# logi-mark1-edu.net
KiCad netlist of a schematic drawn in Altium Designer
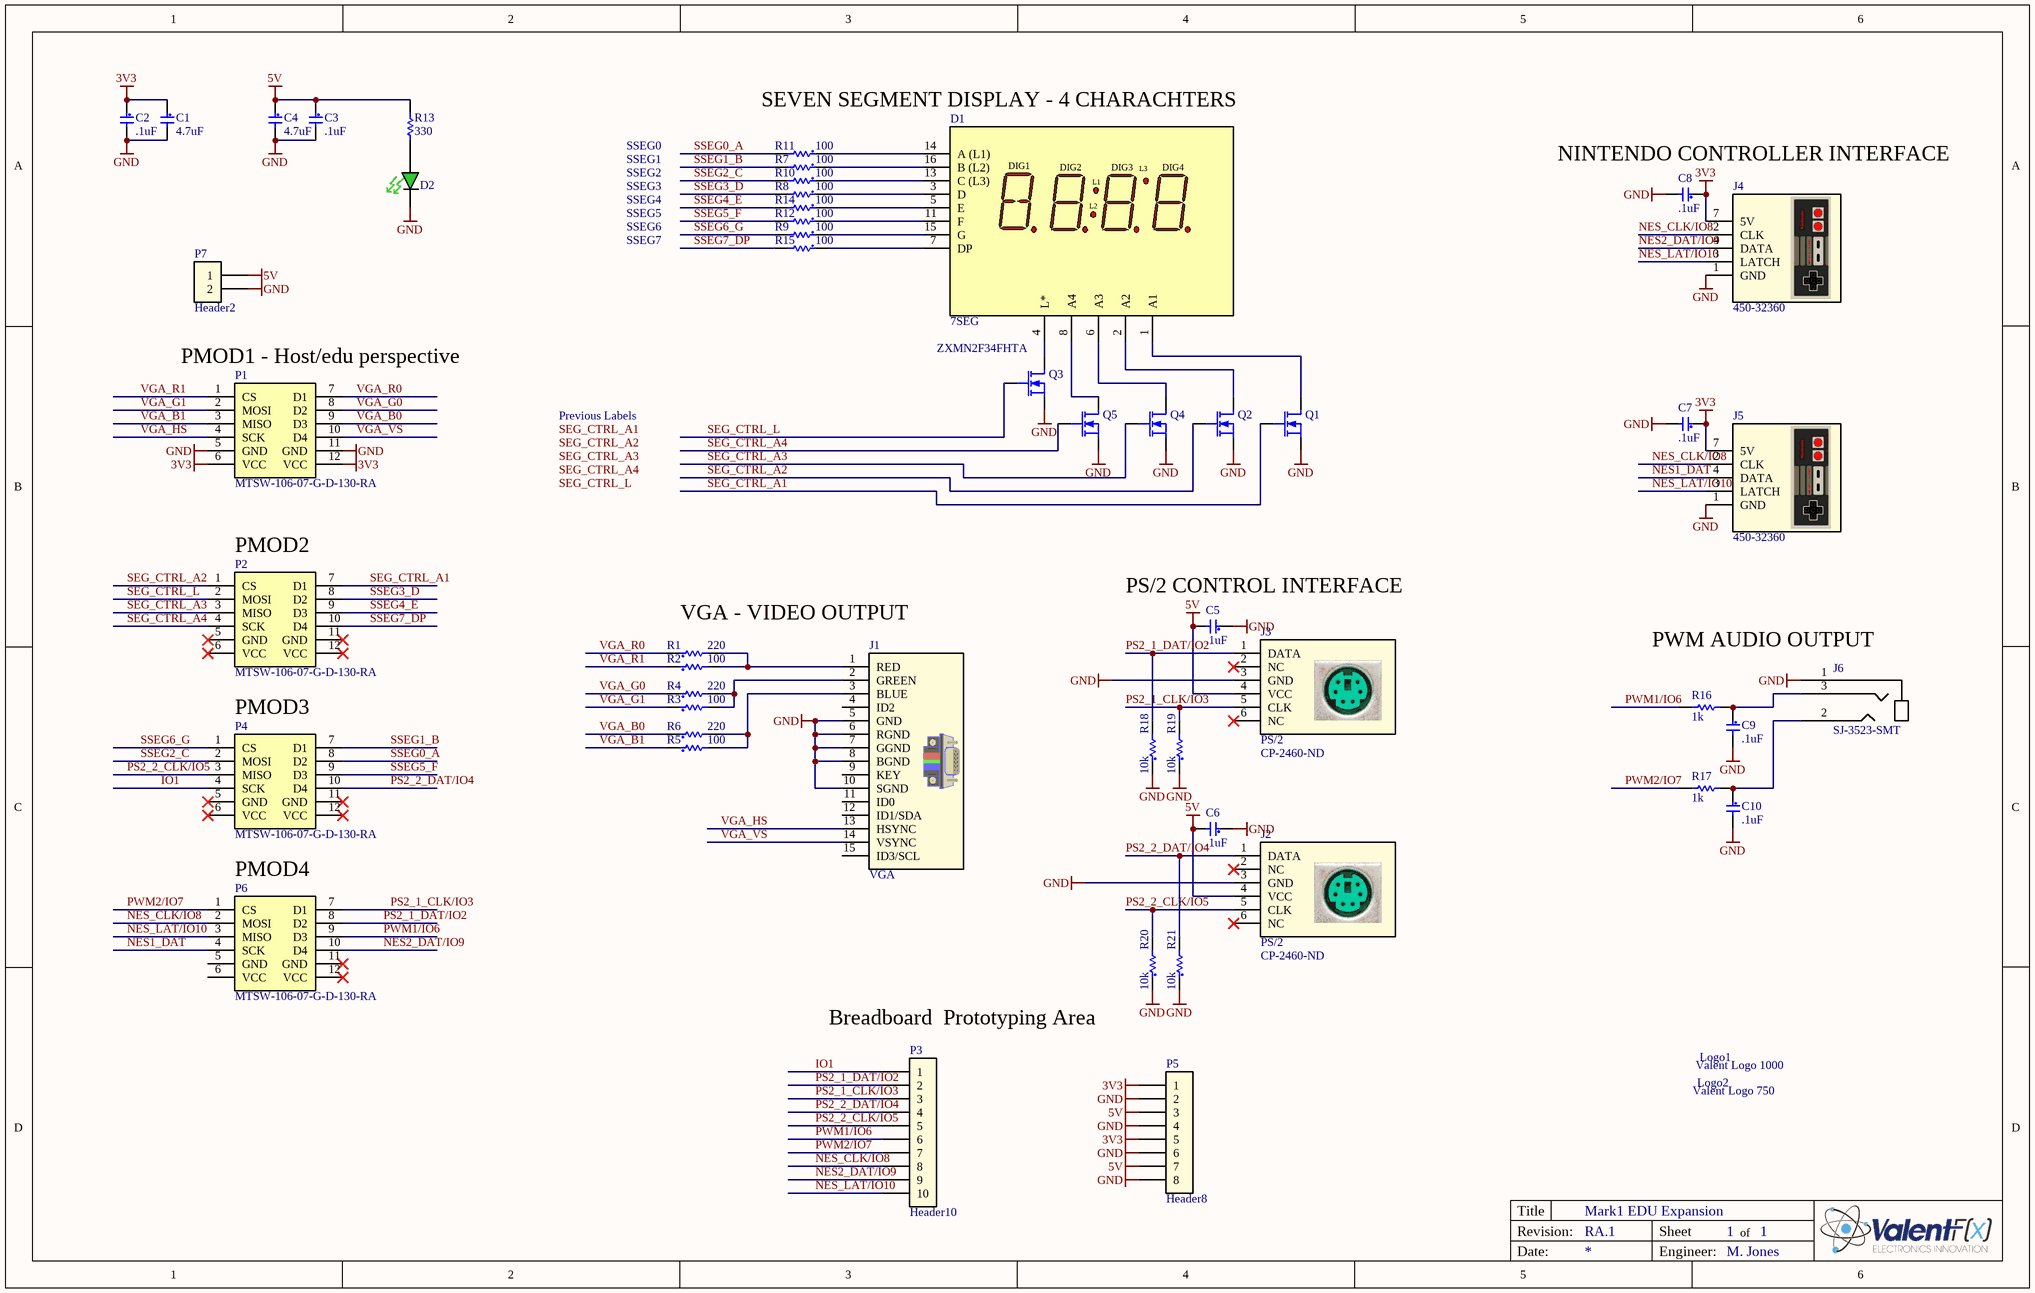
[diagram p0: logi-mark1-edu.SchDoc]

(export (version "E")
  (design (tool "Eeschema 10.0.6"))
  (components
    (comp (ref "C1")
      (value "4.7uF")
      (footprint "mRCL:C0603")
      (description "4.7uF 10volts Y5V +80-20% (MLCC) - SMD/SMT 0603")
      (fields
        (field (name "MANUFACTURER") "Murata")
        (field (name "MANUFACTURER PART NUMBER") "GRM188F51A475ZE20D")
      )
      (libsource (lib "mCapacitors") (part "C0603 - GRM188F51A475ZE20D"))
    )
    (comp (ref "C2")
      (value ".1uF")
      (footprint "mRCL:C0603")
      (description "0.1uF 50volts X7R 10% MLCC SMD/SMT 0603")
      (fields
        (field (name "MANUFACTURER") "Murata")
        (field (name "MANUFACTURER PART NUMBER") "GRM188R71H104KA93D")
      )
      (libsource (lib "mCapacitors") (part "C0603 - GRM188R71H104KA93D"))
    )
    (comp (ref "C3")
      (value ".1uF")
      (footprint "mRCL:C0603")
      (description "0.1uF 50volts X7R 10% MLCC SMD/SMT 0603")
      (fields
        (field (name "MANUFACTURER") "Murata")
        (field (name "MANUFACTURER PART NUMBER") "GRM188R71H104KA93D")
      )
      (libsource (lib "mCapacitors") (part "C0603 - GRM188R71H104KA93D"))
    )
    (comp (ref "C4")
      (value "4.7uF")
      (footprint "mRCL:C0603")
      (description "4.7uF 10volts Y5V +80-20% (MLCC) - SMD/SMT 0603")
      (fields
        (field (name "MANUFACTURER") "Murata")
        (field (name "MANUFACTURER PART NUMBER") "GRM188F51A475ZE20D")
      )
      (libsource (lib "mCapacitors") (part "C0603 - GRM188F51A475ZE20D"))
    )
    (comp (ref "C5")
      (value ".1uF")
      (footprint "mRCL:C0603")
      (description "0.1uF 50volts X7R 10% MLCC SMD/SMT 0603")
      (fields
        (field (name "MANUFACTURER") "Murata")
        (field (name "MANUFACTURER PART NUMBER") "GRM188R71H104KA93D")
      )
      (libsource (lib "mCapacitors") (part "C0603 - GRM188R71H104KA93D"))
    )
    (comp (ref "C6")
      (value ".1uF")
      (footprint "mRCL:C0603")
      (description "0.1uF 50volts X7R 10% MLCC SMD/SMT 0603")
      (fields
        (field (name "MANUFACTURER") "Murata")
        (field (name "MANUFACTURER PART NUMBER") "GRM188R71H104KA93D")
      )
      (libsource (lib "mCapacitors") (part "C0603 - GRM188R71H104KA93D"))
    )
    (comp (ref "C7")
      (value ".1uF")
      (footprint "mRCL:C0603")
      (description "0.1uF 50volts X7R 10% MLCC SMD/SMT 0603")
      (fields
        (field (name "MANUFACTURER") "Murata")
        (field (name "MANUFACTURER PART NUMBER") "GRM188R71H104KA93D")
      )
      (libsource (lib "mCapacitors") (part "C0603 - GRM188R71H104KA93D"))
    )
    (comp (ref "C8")
      (value ".1uF")
      (footprint "mRCL:C0603")
      (description "0.1uF 50volts X7R 10% MLCC SMD/SMT 0603")
      (fields
        (field (name "MANUFACTURER") "Murata")
        (field (name "MANUFACTURER PART NUMBER") "GRM188R71H104KA93D")
      )
      (libsource (lib "mCapacitors") (part "C0603 - GRM188R71H104KA93D"))
    )
    (comp (ref "C9")
      (value ".1uF")
      (footprint "mRCL:C0603")
      (description "0.1uF 50volts X7R 10% MLCC SMD/SMT 0603")
      (fields
        (field (name "MANUFACTURER") "Murata")
        (field (name "MANUFACTURER PART NUMBER") "GRM188R71H104KA93D")
      )
      (libsource (lib "mCapacitors") (part "C0603 - GRM188R71H104KA93D"))
    )
    (comp (ref "C10")
      (value ".1uF")
      (footprint "mRCL:C0603")
      (description "0.1uF 50volts X7R 10% MLCC SMD/SMT 0603")
      (fields
        (field (name "MANUFACTURER") "Murata")
        (field (name "MANUFACTURER PART NUMBER") "GRM188R71H104KA93D")
      )
      (libsource (lib "mCapacitors") (part "C0603 - GRM188R71H104KA93D"))
    )
    (comp (ref "D1")
      (value "7SEG")
      (footprint "LED - SSEG - LTC-4727JR")
      (description "LED Displays & Accessories 4 Digit, Red Low Current")
      (fields (field (name "MANUFACTURER") "Lite-On") (field (name "MANUFACTURER PART NUMBER") "LTC-4727JR"))
      (libsource (lib "eDiode") (part "LED - SSEG - LTC-4727JR"))
    )
    (comp (ref "D2")
      (value "LED 1.6X0.8MM 570NM GRN CLR SMD")
      (footprint "LED_0603 - GREEN")
      (fields
        (field (name "MANUFACTURER") "Kingbright Corp")
        (field (name "MANUFACTURER PART NUMBER") "APT1608CGCK")
      )
      (libsource (lib "eDiode") (part "APT1608CGCK"))
    )
    (comp (ref "J1")
      (value "VGA")
      (footprint "econnector:1-1734530-1")
      (description "CONN HD D-SUB RCPT R/A 15POS")
      (fields
        (field (name "MANUFACTURER") "TE Connectivity")
        (field (name "MANUFACTURER PART NUMBER") "1-1734530-1")
      )
      (libsource (lib "eConnector") (part "VGA - 1-1734530-1"))
    )
    (comp (ref "J2")
      (value "PS/2")
      (footprint "mconnector:MD-60S - PS/2")
      (description "CONN MINIDIN RECPT UNSHIELD 6POS - PS/2 mouse - keybaord")
      (fields
        (field (name "MANUFACTURER") "CUI Inc")
        (field (name "MANUFACTURER PART NUMBER") "MD-60S")
        (field (name "SUPPLIER PART NUMBER 1") "CP-2460-ND")
      )
      (libsource (lib "mConnector") (part "Con - D-60S"))
    )
    (comp (ref "J3")
      (value "PS/2")
      (footprint "mconnector:MD-60S - PS/2")
      (description "CONN MINIDIN RECPT UNSHIELD 6POS - PS/2 mouse - keybaord")
      (fields
        (field (name "MANUFACTURER") "CUI Inc")
        (field (name "MANUFACTURER PART NUMBER") "MD-60S")
        (field (name "SUPPLIER PART NUMBER 1") "CP-2460-ND")
      )
      (libsource (lib "mConnector") (part "Con - D-60S"))
    )
    (comp (ref "J4")
      (value "450-32360")
      (footprint "NES - 450-32360")
      (description "NES CONTROLLER SOCKET")
      (fields (field (name "MANUFACTURER") "Parallax Inc"))
      (libsource (lib "mConnector") (part "450-32360"))
    )
    (comp (ref "J5")
      (value "450-32360")
      (footprint "NES - 450-32360")
      (description "NES CONTROLLER SOCKET")
      (fields (field (name "MANUFACTURER") "Parallax Inc"))
      (libsource (lib "mConnector") (part "450-32360"))
    )
    (comp (ref "J6")
      (value "SJ-3523-SMT")
      (footprint "SJ-3523-SMT")
      (description "CONN AUDIO JACK 3.5MM STEREO SMD")
      (fields (field (name "MANUFACTURER") "CUI Inc") (field (name "SOURCE") "Digikey"))
      (libsource (lib "eConnector") (part "SJ-3523-SMT"))
    )
    (comp (ref "Logo1")
      (value "Valent Logo 1000")
      (footprint "ValentFX_1000")
      (libsource (lib "mLogos") (part "Valent Logo 1000"))
    )
    (comp (ref "Logo2")
      (value "Valent Logo 750")
      (footprint "ValentFX_750")
      (libsource (lib "mLogos") (part "Valent Logo 750"))
    )
    (comp (ref "P1")
      (value "MTSW-106-07-G-D-130-RA")
      (footprint "mconnector:PMOD HEADER - Male")
      (description "Samtec Male Conn Unshrouded Header HDR 12 POS 2.54mm Solder RA Thru-Hole")
      (fields (field (name "MANUFACTURER") "Samtec"))
      (libsource (lib "mConnector") (part "P-MOD - MTSW-106-07-G-D-130-RA"))
    )
    (comp (ref "P2")
      (value "MTSW-106-07-G-D-130-RA")
      (footprint "mconnector:PMOD HEADER - Male")
      (description "Samtec Male Conn Unshrouded Header HDR 12 POS 2.54mm Solder RA Thru-Hole")
      (fields (field (name "MANUFACTURER") "Samtec"))
      (libsource (lib "mConnector") (part "P-MOD - MTSW-106-07-G-D-130-RA"))
    )
    (comp (ref "P3")
      (value "Header10")
      (footprint "HEADER_10_40_100THRU SIP")
      (description "Header 10 pin")
      (libsource (lib "mConnector") (part "Header10"))
    )
    (comp (ref "P4")
      (value "MTSW-106-07-G-D-130-RA")
      (footprint "mconnector:PMOD HEADER - Male")
      (description "Samtec Male Conn Unshrouded Header HDR 12 POS 2.54mm Solder RA Thru-Hole")
      (fields (field (name "MANUFACTURER") "Samtec"))
      (libsource (lib "mConnector") (part "P-MOD - MTSW-106-07-G-D-130-RA"))
    )
    (comp (ref "P5")
      (value "Header8")
      (footprint "HEADER_8_40_100THRU SIP")
      (description "Header 8 pin")
      (libsource (lib "mConnector") (part "Header8"))
    )
    (comp (ref "P6")
      (value "MTSW-106-07-G-D-130-RA")
      (footprint "mconnector:PMOD HEADER - Male")
      (description "Samtec Male Conn Unshrouded Header HDR 12 POS 2.54mm Solder RA Thru-Hole")
      (fields (field (name "MANUFACTURER") "Samtec"))
      (libsource (lib "mConnector") (part "P-MOD - MTSW-106-07-G-D-130-RA"))
    )
    (comp (ref "P7")
      (value "Header2")
      (footprint "HEADER_2_40_100 THRU SIP")
      (description "Header 2 pin")
      (libsource (lib "mConnector") (part "Header2"))
    )
    (comp (ref "Q1")
      (value "ZXMN2F34FHTA")
      (footprint "SOT-23")
      (description "MOSFET N-CHAN 20V SOT23-3")
      (fields (field (name "MANUFACTURER") "Diodes/Zetex"))
      (libsource (lib "eTransistor") (part "ZXMN2F34FHTA"))
    )
    (comp (ref "Q2")
      (value "ZXMN2F34FHTA")
      (footprint "SOT-23")
      (description "MOSFET N-CHAN 20V SOT23-3")
      (fields (field (name "MANUFACTURER") "Diodes/Zetex"))
      (libsource (lib "eTransistor") (part "ZXMN2F34FHTA"))
    )
    (comp (ref "Q3")
      (value "ZXMN2F34FHTA")
      (footprint "SOT-23")
      (description "MOSFET N-CHAN 20V SOT23-3")
      (fields (field (name "MANUFACTURER") "Diodes/Zetex"))
      (libsource (lib "eTransistor") (part "ZXMN2F34FHTA"))
    )
    (comp (ref "Q4")
      (value "ZXMN2F34FHTA")
      (footprint "SOT-23")
      (description "MOSFET N-CHAN 20V SOT23-3")
      (fields (field (name "MANUFACTURER") "Diodes/Zetex"))
      (libsource (lib "eTransistor") (part "ZXMN2F34FHTA"))
    )
    (comp (ref "Q5")
      (value "ZXMN2F34FHTA")
      (footprint "SOT-23")
      (description "MOSFET N-CHAN 20V SOT23-3")
      (fields (field (name "MANUFACTURER") "Diodes/Zetex"))
      (libsource (lib "eTransistor") (part "ZXMN2F34FHTA"))
    )
    (comp (ref "R1")
      (value "220")
      (footprint "mRCL:R0603")
      (description "220 - thick Film Resistors - SMD 0603 220ohms 1% Tol")
      (fields
        (field (name "MANUFACTURER") "Panasonic - ECG")
        (field (name "MANUFACTURER PART NUMBER") "ERJ-3EKF2200V")
      )
      (libsource (lib "mResistors") (part "R0603 - ERJ-3EKF2200V"))
    )
    (comp (ref "R2")
      (value "100")
      (footprint "mRCL:R0603")
      (description "100 ohms 1% Thick Film Resistors - SMD 1/10watt")
      (fields
        (field (name "MANUFACTURER") "Vishay/Dale")
        (field (name "MANUFACTURER PART NUMBER") "CRCW0603100RFKEA")
      )
      (libsource (lib "mResistors") (part "R0603 - CRCW0603100RFKEA"))
    )
    (comp (ref "R3")
      (value "100")
      (footprint "mRCL:R0603")
      (description "100 ohms 1% Thick Film Resistors - SMD 1/10watt")
      (fields
        (field (name "MANUFACTURER") "Vishay/Dale")
        (field (name "MANUFACTURER PART NUMBER") "CRCW0603100RFKEA")
      )
      (libsource (lib "mResistors") (part "R0603 - CRCW0603100RFKEA"))
    )
    (comp (ref "R4")
      (value "220")
      (footprint "mRCL:R0603")
      (description "220 - thick Film Resistors - SMD 0603 220ohms 1% Tol")
      (fields
        (field (name "MANUFACTURER") "Panasonic - ECG")
        (field (name "MANUFACTURER PART NUMBER") "ERJ-3EKF2200V")
      )
      (libsource (lib "mResistors") (part "R0603 - ERJ-3EKF2200V"))
    )
    (comp (ref "R5")
      (value "100")
      (footprint "mRCL:R0603")
      (description "100 ohms 1% Thick Film Resistors - SMD 1/10watt")
      (fields
        (field (name "MANUFACTURER") "Vishay/Dale")
        (field (name "MANUFACTURER PART NUMBER") "CRCW0603100RFKEA")
      )
      (libsource (lib "mResistors") (part "R0603 - CRCW0603100RFKEA"))
    )
    (comp (ref "R6")
      (value "220")
      (footprint "mRCL:R0603")
      (description "220 - thick Film Resistors - SMD 0603 220ohms 1% Tol")
      (fields
        (field (name "MANUFACTURER") "Panasonic - ECG")
        (field (name "MANUFACTURER PART NUMBER") "ERJ-3EKF2200V")
      )
      (libsource (lib "mResistors") (part "R0603 - ERJ-3EKF2200V"))
    )
    (comp (ref "R7")
      (value "100")
      (footprint "R0603")
      (description "RES 10.0K OHM 1/10W 1% 0603 SMD")
      (fields
        (field (name "MANUFACTURER") "Panasonic - ECG")
        (field (name "MANUFACTURER PART NUMBER") "ERJ-3EKF1002V")
      )
      (libsource (lib "myGeneral") (part "Res-Eli"))
    )
    (comp (ref "R8")
      (value "100")
      (footprint "R0603")
      (description "RES 10.0K OHM 1/10W 1% 0603 SMD")
      (fields
        (field (name "MANUFACTURER") "Panasonic - ECG")
        (field (name "MANUFACTURER PART NUMBER") "ERJ-3EKF1002V")
      )
      (libsource (lib "myGeneral") (part "Res-Eli"))
    )
    (comp (ref "R9")
      (value "100")
      (footprint "R0603")
      (description "RES 10.0K OHM 1/10W 1% 0603 SMD")
      (fields
        (field (name "MANUFACTURER") "Panasonic - ECG")
        (field (name "MANUFACTURER PART NUMBER") "ERJ-3EKF1002V")
      )
      (libsource (lib "myGeneral") (part "Res-Eli"))
    )
    (comp (ref "R10")
      (value "100")
      (footprint "R0603")
      (description "RES 10.0K OHM 1/10W 1% 0603 SMD")
      (fields
        (field (name "MANUFACTURER") "Panasonic - ECG")
        (field (name "MANUFACTURER PART NUMBER") "ERJ-3EKF1002V")
      )
      (libsource (lib "myGeneral") (part "Res-Eli"))
    )
    (comp (ref "R11")
      (value "100")
      (footprint "R0603")
      (description "RES 10.0K OHM 1/10W 1% 0603 SMD")
      (fields
        (field (name "MANUFACTURER") "Panasonic - ECG")
        (field (name "MANUFACTURER PART NUMBER") "ERJ-3EKF1002V")
      )
      (libsource (lib "myGeneral") (part "Res-Eli"))
    )
    (comp (ref "R12")
      (value "100")
      (footprint "R0603")
      (description "RES 10.0K OHM 1/10W 1% 0603 SMD")
      (fields
        (field (name "MANUFACTURER") "Panasonic - ECG")
        (field (name "MANUFACTURER PART NUMBER") "ERJ-3EKF1002V")
      )
      (libsource (lib "myGeneral") (part "Res-Eli"))
    )
    (comp (ref "R13")
      (value "330")
      (footprint "R0603")
      (description "RES 330 OHM 1/10W 1% 0603 SMD")
      (fields
        (field (name "MANUFACTURER") "Panasonic - ECG")
        (field (name "MANUFACTURER PART NUMBER") "ERJ-3EKF3300V")
      )
      (libsource (lib "eResistors") (part "ERJ-3EKF3300V"))
    )
    (comp (ref "R14")
      (value "100")
      (footprint "R0603")
      (description "RES 10.0K OHM 1/10W 1% 0603 SMD")
      (fields
        (field (name "MANUFACTURER") "Panasonic - ECG")
        (field (name "MANUFACTURER PART NUMBER") "ERJ-3EKF1002V")
      )
      (libsource (lib "myGeneral") (part "Res-Eli"))
    )
    (comp (ref "R15")
      (value "100")
      (footprint "R0603")
      (description "RES 10.0K OHM 1/10W 1% 0603 SMD")
      (fields
        (field (name "MANUFACTURER") "Panasonic - ECG")
        (field (name "MANUFACTURER PART NUMBER") "ERJ-3EKF1002V")
      )
      (libsource (lib "myGeneral") (part "Res-Eli"))
    )
    (comp (ref "R16")
      (value "1k")
      (footprint "R0603")
      (description "RES 1.00K OHM 1/10W 1% 0603 SMD")
      (fields
        (field (name "MANUFACTURER") "Panasonic - ECG")
        (field (name "MANUFACTURER PART NUMBER") "ERJ-3EKF1001V")
      )
      (libsource (lib "eResistors") (part "ERJ-3EKF1001V"))
    )
    (comp (ref "R17")
      (value "1k")
      (footprint "R0603")
      (description "RES 1.00K OHM 1/10W 1% 0603 SMD")
      (fields
        (field (name "MANUFACTURER") "Panasonic - ECG")
        (field (name "MANUFACTURER PART NUMBER") "ERJ-3EKF1001V")
      )
      (libsource (lib "eResistors") (part "ERJ-3EKF1001V"))
    )
    (comp (ref "R18")
      (value "10k")
      (footprint "mRCL:R0603")
      (description "10k Thick Film Resistors - SMD 1/10watt 10Kohms 1%")
      (fields
        (field (name "MANUFACTURER") "Vishay Dale")
        (field (name "MANUFACTURER PART NUMBER") "CRCW060310K0FKEA")
      )
      (libsource (lib "mResistors") (part "R0603 - CRCW060310K0FKEA"))
    )
    (comp (ref "R19")
      (value "10k")
      (footprint "mRCL:R0603")
      (description "10k Thick Film Resistors - SMD 1/10watt 10Kohms 1%")
      (fields
        (field (name "MANUFACTURER") "Vishay Dale")
        (field (name "MANUFACTURER PART NUMBER") "CRCW060310K0FKEA")
      )
      (libsource (lib "mResistors") (part "R0603 - CRCW060310K0FKEA"))
    )
    (comp (ref "R20")
      (value "10k")
      (footprint "mRCL:R0603")
      (description "10k Thick Film Resistors - SMD 1/10watt 10Kohms 1%")
      (fields
        (field (name "MANUFACTURER") "Vishay Dale")
        (field (name "MANUFACTURER PART NUMBER") "CRCW060310K0FKEA")
      )
      (libsource (lib "mResistors") (part "R0603 - CRCW060310K0FKEA"))
    )
    (comp (ref "R21")
      (value "10k")
      (footprint "mRCL:R0603")
      (description "10k Thick Film Resistors - SMD 1/10watt 10Kohms 1%")
      (fields
        (field (name "MANUFACTURER") "Vishay Dale")
        (field (name "MANUFACTURER PART NUMBER") "CRCW060310K0FKEA")
      )
      (libsource (lib "mResistors") (part "R0603 - CRCW060310K0FKEA"))
    )
  )
  (nets
    (net (code "1") (name "/IO1") (class "Default")
      (node (ref "P3") (pin "1") (pinfunction "1_1") (pintype "passive"))
      (node (ref "P4") (pin "4") (pinfunction "SCK_4") (pintype "power_in"))
    )
    (net (code "2") (name "/NES1_DAT") (class "Default")
      (node (ref "J5") (pin "4") (pinfunction "DATA_4") (pintype "passive"))
      (node (ref "P6") (pin "4") (pinfunction "SCK_4") (pintype "power_in"))
    )
    (net (code "3") (name "/NES2_DAT{slash}IO9") (class "Default")
      (node (ref "J4") (pin "4") (pinfunction "DATA_4") (pintype "passive"))
      (node (ref "P3") (pin "9") (pinfunction "9_9") (pintype "passive"))
      (node (ref "P6") (pin "10") (pinfunction "D4_10") (pintype "power_in"))
    )
    (net (code "4") (name "/NES_CLK{slash}IO8") (class "Default")
      (node (ref "J4") (pin "2") (pinfunction "CLK_2") (pintype "passive"))
      (node (ref "J5") (pin "2") (pinfunction "CLK_2") (pintype "passive"))
      (node (ref "P3") (pin "8") (pinfunction "8_8") (pintype "passive"))
      (node (ref "P6") (pin "2") (pinfunction "MOSI_2") (pintype "power_in"))
    )
    (net (code "5") (name "/NES_LAT{slash}IO10") (class "Default")
      (node (ref "J4") (pin "3") (pinfunction "LATCH_3") (pintype "passive"))
      (node (ref "J5") (pin "3") (pinfunction "LATCH_3") (pintype "passive"))
      (node (ref "P3") (pin "10") (pinfunction "10_10") (pintype "passive"))
      (node (ref "P6") (pin "3") (pinfunction "MISO_3") (pintype "power_in"))
    )
    (net (code "6") (name "/PS2_1_CLK{slash}IO3") (class "Default")
      (node (ref "J3") (pin "5") (pinfunction "CLK_5") (pintype "passive"))
      (node (ref "P3") (pin "3") (pinfunction "3_3") (pintype "passive"))
      (node (ref "P6") (pin "7") (pinfunction "D1_7") (pintype "power_in"))
      (node (ref "R19") (pin "2") (pinfunction "2_2") (pintype "passive"))
    )
    (net (code "7") (name "/PS2_1_DAT{slash}IO2") (class "Default")
      (node (ref "J3") (pin "1") (pinfunction "DATA_1") (pintype "passive"))
      (node (ref "P3") (pin "2") (pinfunction "2_2") (pintype "passive"))
      (node (ref "P6") (pin "8") (pinfunction "D2_8") (pintype "power_in"))
      (node (ref "R18") (pin "2") (pinfunction "2_2") (pintype "passive"))
    )
    (net (code "8") (name "/PS2_2_CLK{slash}IO5") (class "Default")
      (node (ref "J2") (pin "5") (pinfunction "CLK_5") (pintype "passive"))
      (node (ref "P3") (pin "5") (pinfunction "5_5") (pintype "passive"))
      (node (ref "P4") (pin "3") (pinfunction "MISO_3") (pintype "power_in"))
      (node (ref "R20") (pin "2") (pinfunction "2_2") (pintype "passive"))
    )
    (net (code "9") (name "/PS2_2_DAT{slash}IO4") (class "Default")
      (node (ref "J2") (pin "1") (pinfunction "DATA_1") (pintype "passive"))
      (node (ref "P3") (pin "4") (pinfunction "4_4") (pintype "passive"))
      (node (ref "P4") (pin "10") (pinfunction "D4_10") (pintype "power_in"))
      (node (ref "R21") (pin "2") (pinfunction "2_2") (pintype "passive"))
    )
    (net (code "10") (name "/PWM1{slash}IO6") (class "Default")
      (node (ref "P3") (pin "6") (pinfunction "6_6") (pintype "passive"))
      (node (ref "P6") (pin "9") (pinfunction "D3_9") (pintype "power_in"))
      (node (ref "R16") (pin "1") (pinfunction "1_1") (pintype "passive"))
    )
    (net (code "11") (name "/PWM2{slash}IO7") (class "Default")
      (node (ref "P3") (pin "7") (pinfunction "7_7") (pintype "passive"))
      (node (ref "P6") (pin "1") (pinfunction "CS_1") (pintype "power_in"))
      (node (ref "R17") (pin "1") (pinfunction "1_1") (pintype "passive"))
    )
    (net (code "12") (name "/SEG_CTRL_A1") (class "Default")
      (node (ref "P2") (pin "7") (pinfunction "D1_7") (pintype "power_in"))
      (node (ref "Q1") (pin "1") (pinfunction "G_1") (pintype "passive"))
    )
    (net (code "13") (name "/SEG_CTRL_A2") (class "Default")
      (node (ref "P2") (pin "1") (pinfunction "CS_1") (pintype "power_in"))
      (node (ref "Q2") (pin "1") (pinfunction "G_1") (pintype "passive"))
    )
    (net (code "14") (name "/SEG_CTRL_A3") (class "Default")
      (node (ref "P2") (pin "3") (pinfunction "MISO_3") (pintype "power_in"))
      (node (ref "Q4") (pin "1") (pinfunction "G_1") (pintype "passive"))
    )
    (net (code "15") (name "/SEG_CTRL_A4") (class "Default")
      (node (ref "P2") (pin "4") (pinfunction "SCK_4") (pintype "power_in"))
      (node (ref "Q5") (pin "1") (pinfunction "G_1") (pintype "passive"))
    )
    (net (code "16") (name "/SEG_CTRL_L") (class "Default")
      (node (ref "P2") (pin "2") (pinfunction "MOSI_2") (pintype "power_in"))
      (node (ref "Q3") (pin "1") (pinfunction "G_1") (pintype "passive"))
    )
    (net (code "17") (name "/SSEG0_A") (class "Default")
      (node (ref "P4") (pin "8") (pinfunction "D2_8") (pintype "power_in"))
      (node (ref "R11") (pin "2") (pinfunction "2_2") (pintype "passive"))
    )
    (net (code "18") (name "/SSEG1_B") (class "Default")
      (node (ref "P4") (pin "7") (pinfunction "D1_7") (pintype "power_in"))
      (node (ref "R7") (pin "2") (pinfunction "2_2") (pintype "passive"))
    )
    (net (code "19") (name "/SSEG2_C") (class "Default")
      (node (ref "P4") (pin "2") (pinfunction "MOSI_2") (pintype "power_in"))
      (node (ref "R10") (pin "2") (pinfunction "2_2") (pintype "passive"))
    )
    (net (code "20") (name "/SSEG3_D") (class "Default")
      (node (ref "P2") (pin "8") (pinfunction "D2_8") (pintype "power_in"))
      (node (ref "R8") (pin "2") (pinfunction "2_2") (pintype "passive"))
    )
    (net (code "21") (name "/SSEG4_E") (class "Default")
      (node (ref "P2") (pin "9") (pinfunction "D3_9") (pintype "power_in"))
      (node (ref "R14") (pin "2") (pinfunction "2_2") (pintype "passive"))
    )
    (net (code "22") (name "/SSEG5_F") (class "Default")
      (node (ref "P4") (pin "9") (pinfunction "D3_9") (pintype "power_in"))
      (node (ref "R12") (pin "2") (pinfunction "2_2") (pintype "passive"))
    )
    (net (code "23") (name "/SSEG6_G") (class "Default")
      (node (ref "P4") (pin "1") (pinfunction "CS_1") (pintype "power_in"))
      (node (ref "R9") (pin "2") (pinfunction "2_2") (pintype "passive"))
    )
    (net (code "24") (name "/SSEG7_DP") (class "Default")
      (node (ref "P2") (pin "10") (pinfunction "D4_10") (pintype "power_in"))
      (node (ref "R15") (pin "2") (pinfunction "2_2") (pintype "passive"))
    )
    (net (code "25") (name "/VGA_B0") (class "Default")
      (node (ref "P1") (pin "9") (pinfunction "D3_9") (pintype "power_in"))
      (node (ref "R6") (pin "1") (pinfunction "1_1") (pintype "passive"))
    )
    (net (code "26") (name "/VGA_B1") (class "Default")
      (node (ref "P1") (pin "3") (pinfunction "MISO_3") (pintype "power_in"))
      (node (ref "R5") (pin "1") (pinfunction "1_1") (pintype "passive"))
    )
    (net (code "27") (name "/VGA_G0") (class "Default")
      (node (ref "P1") (pin "8") (pinfunction "D2_8") (pintype "power_in"))
      (node (ref "R4") (pin "1") (pinfunction "1_1") (pintype "passive"))
    )
    (net (code "28") (name "/VGA_G1") (class "Default")
      (node (ref "P1") (pin "2") (pinfunction "MOSI_2") (pintype "power_in"))
      (node (ref "R3") (pin "1") (pinfunction "1_1") (pintype "passive"))
    )
    (net (code "29") (name "/VGA_HS") (class "Default")
      (node (ref "J1") (pin "13") (pinfunction "HSYNC_13") (pintype "passive"))
      (node (ref "P1") (pin "4") (pinfunction "SCK_4") (pintype "power_in"))
    )
    (net (code "30") (name "/VGA_R0") (class "Default")
      (node (ref "P1") (pin "7") (pinfunction "D1_7") (pintype "power_in"))
      (node (ref "R1") (pin "1") (pinfunction "1_1") (pintype "passive"))
    )
    (net (code "31") (name "/VGA_R1") (class "Default")
      (node (ref "P1") (pin "1") (pinfunction "CS_1") (pintype "power_in"))
      (node (ref "R2") (pin "1") (pinfunction "1_1") (pintype "passive"))
    )
    (net (code "32") (name "/VGA_VS") (class "Default")
      (node (ref "J1") (pin "14") (pinfunction "VSYNC_14") (pintype "passive"))
      (node (ref "P1") (pin "10") (pinfunction "D4_10") (pintype "power_in"))
    )
    (net (code "33") (name "3V3") (class "Default")
      (node (ref "C1") (pin "1") (pinfunction "1_1") (pintype "passive"))
      (node (ref "C2") (pin "1") (pinfunction "1_1") (pintype "passive"))
      (node (ref "C7") (pin "1") (pinfunction "1_1") (pintype "passive"))
      (node (ref "C8") (pin "1") (pinfunction "1_1") (pintype "passive"))
      (node (ref "J4") (pin "7") (pinfunction "5V_7") (pintype "passive"))
      (node (ref "J5") (pin "7") (pinfunction "5V_7") (pintype "passive"))
      (node (ref "P1") (pin "12") (pinfunction "VCC_12") (pintype "power_in"))
      (node (ref "P1") (pin "6") (pinfunction "VCC_6") (pintype "power_in"))
      (node (ref "P5") (pin "1") (pinfunction "1_1") (pintype "passive"))
      (node (ref "P5") (pin "5") (pinfunction "5_5") (pintype "passive"))
    )
    (net (code "34") (name "5V") (class "Default")
      (node (ref "C3") (pin "1") (pinfunction "1_1") (pintype "passive"))
      (node (ref "C4") (pin "1") (pinfunction "1_1") (pintype "passive"))
      (node (ref "C5") (pin "2") (pinfunction "2_2") (pintype "passive"))
      (node (ref "C6") (pin "2") (pinfunction "2_2") (pintype "passive"))
      (node (ref "J2") (pin "4") (pinfunction "VCC_4") (pintype "passive"))
      (node (ref "J3") (pin "4") (pinfunction "VCC_4") (pintype "passive"))
      (node (ref "P5") (pin "3") (pinfunction "3_3") (pintype "passive"))
      (node (ref "P5") (pin "7") (pinfunction "7_7") (pintype "passive"))
      (node (ref "P7") (pin "1") (pinfunction "1_1") (pintype "passive"))
      (node (ref "R13") (pin "1") (pinfunction "1_1") (pintype "passive"))
    )
    (net (code "35") (name "GND") (class "Default")
      (node (ref "C1") (pin "2") (pinfunction "2_2") (pintype "passive"))
      (node (ref "C10") (pin "2") (pinfunction "2_2") (pintype "passive"))
      (node (ref "C2") (pin "2") (pinfunction "2_2") (pintype "passive"))
      (node (ref "C3") (pin "2") (pinfunction "2_2") (pintype "passive"))
      (node (ref "C4") (pin "2") (pinfunction "2_2") (pintype "passive"))
      (node (ref "C5") (pin "1") (pinfunction "1_1") (pintype "passive"))
      (node (ref "C6") (pin "1") (pinfunction "1_1") (pintype "passive"))
      (node (ref "C7") (pin "2") (pinfunction "2_2") (pintype "passive"))
      (node (ref "C8") (pin "2") (pinfunction "2_2") (pintype "passive"))
      (node (ref "C9") (pin "2") (pinfunction "2_2") (pintype "passive"))
      (node (ref "D2") (pin "C") (pinfunction "C_C") (pintype "passive"))
      (node (ref "J1") (pin "10") (pinfunction "SGND_10") (pintype "passive"))
      (node (ref "J1") (pin "5") (pinfunction "GND_5") (pintype "passive"))
      (node (ref "J1") (pin "6") (pinfunction "RGND_6") (pintype "passive"))
      (node (ref "J1") (pin "7") (pinfunction "GGND_7") (pintype "passive"))
      (node (ref "J1") (pin "8") (pinfunction "BGND_8") (pintype "passive"))
      (node (ref "J2") (pin "3") (pinfunction "GND_3") (pintype "passive"))
      (node (ref "J3") (pin "3") (pinfunction "GND_3") (pintype "passive"))
      (node (ref "J4") (pin "1") (pinfunction "GND_1") (pintype "passive"))
      (node (ref "J5") (pin "1") (pinfunction "GND_1") (pintype "passive"))
      (node (ref "J6") (pin "1") (pinfunction "1_1") (pintype "passive"))
      (node (ref "P1") (pin "11") (pinfunction "GND_11") (pintype "power_in"))
      (node (ref "P1") (pin "5") (pinfunction "GND_5") (pintype "power_in"))
      (node (ref "P5") (pin "2") (pinfunction "2_2") (pintype "passive"))
      (node (ref "P5") (pin "4") (pinfunction "4_4") (pintype "passive"))
      (node (ref "P5") (pin "6") (pinfunction "6_6") (pintype "passive"))
      (node (ref "P5") (pin "8") (pinfunction "8_8") (pintype "passive"))
      (node (ref "P7") (pin "2") (pinfunction "2_2") (pintype "passive"))
      (node (ref "Q1") (pin "2") (pinfunction "2_2") (pintype "passive"))
      (node (ref "Q2") (pin "2") (pinfunction "2_2") (pintype "passive"))
      (node (ref "Q3") (pin "2") (pinfunction "2_2") (pintype "passive"))
      (node (ref "Q4") (pin "2") (pinfunction "2_2") (pintype "passive"))
      (node (ref "Q5") (pin "2") (pinfunction "2_2") (pintype "passive"))
      (node (ref "R18") (pin "1") (pinfunction "1_1") (pintype "passive"))
      (node (ref "R19") (pin "1") (pinfunction "1_1") (pintype "passive"))
      (node (ref "R20") (pin "1") (pinfunction "1_1") (pintype "passive"))
      (node (ref "R21") (pin "1") (pinfunction "1_1") (pintype "passive"))
    )
    (net (code "36") (name "Net-(C9-Pad1)") (class "Default")
      (node (ref "C9") (pin "1") (pinfunction "1_1") (pintype "passive"))
      (node (ref "J6") (pin "3") (pinfunction "3_3") (pintype "passive"))
      (node (ref "R16") (pin "2") (pinfunction "2_2") (pintype "passive"))
    )
    (net (code "37") (name "Net-(C10-Pad1)") (class "Default")
      (node (ref "C10") (pin "1") (pinfunction "1_1") (pintype "passive"))
      (node (ref "J6") (pin "2") (pinfunction "2_2") (pintype "passive"))
      (node (ref "R17") (pin "2") (pinfunction "2_2") (pintype "passive"))
    )
    (net (code "38") (name "Net-(D1-A1)") (class "Default")
      (node (ref "D1") (pin "1") (pinfunction "A1_1") (pintype "passive"))
      (node (ref "Q1") (pin "3") (pinfunction "D_3") (pintype "passive"))
    )
    (net (code "39") (name "Net-(D1-A2)") (class "Default")
      (node (ref "D1") (pin "2") (pinfunction "A2_2") (pintype "passive"))
      (node (ref "Q2") (pin "3") (pinfunction "D_3") (pintype "passive"))
    )
    (net (code "40") (name "Net-(D1-A3)") (class "Default")
      (node (ref "D1") (pin "6") (pinfunction "A3_6") (pintype "passive"))
      (node (ref "Q4") (pin "3") (pinfunction "D_3") (pintype "passive"))
    )
    (net (code "41") (name "Net-(D1-A4)") (class "Default")
      (node (ref "D1") (pin "8") (pinfunction "A4_8") (pintype "passive"))
      (node (ref "Q5") (pin "3") (pinfunction "D_3") (pintype "passive"))
    )
    (net (code "42") (name "Net-(D1-A_(L1))") (class "Default")
      (node (ref "D1") (pin "14") (pinfunction "A_(L1)_14") (pintype "passive"))
      (node (ref "R11") (pin "1") (pinfunction "1_1") (pintype "passive"))
    )
    (net (code "43") (name "Net-(D1-B_(L2))") (class "Default")
      (node (ref "D1") (pin "16") (pinfunction "B_(L2)_16") (pintype "passive"))
      (node (ref "R7") (pin "1") (pinfunction "1_1") (pintype "passive"))
    )
    (net (code "44") (name "Net-(D1-C_(L3))") (class "Default")
      (node (ref "D1") (pin "13") (pinfunction "C_(L3)_13") (pintype "passive"))
      (node (ref "R10") (pin "1") (pinfunction "1_1") (pintype "passive"))
    )
    (net (code "45") (name "Net-(D1-D)") (class "Default")
      (node (ref "D1") (pin "3") (pinfunction "D_3") (pintype "passive"))
      (node (ref "R8") (pin "1") (pinfunction "1_1") (pintype "passive"))
    )
    (net (code "46") (name "Net-(D1-DP)") (class "Default")
      (node (ref "D1") (pin "7") (pinfunction "DP_7") (pintype "passive"))
      (node (ref "R15") (pin "1") (pinfunction "1_1") (pintype "passive"))
    )
    (net (code "47") (name "Net-(D1-E)") (class "Default")
      (node (ref "D1") (pin "5") (pinfunction "E_5") (pintype "passive"))
      (node (ref "R14") (pin "1") (pinfunction "1_1") (pintype "passive"))
    )
    (net (code "48") (name "Net-(D1-F)") (class "Default")
      (node (ref "D1") (pin "11") (pinfunction "F_11") (pintype "passive"))
      (node (ref "R12") (pin "1") (pinfunction "1_1") (pintype "passive"))
    )
    (net (code "49") (name "Net-(D1-G)") (class "Default")
      (node (ref "D1") (pin "15") (pinfunction "G_15") (pintype "passive"))
      (node (ref "R9") (pin "1") (pinfunction "1_1") (pintype "passive"))
    )
    (net (code "50") (name "Net-(D1-L*)") (class "Default")
      (node (ref "D1") (pin "4") (pinfunction "L*_4") (pintype "passive"))
      (node (ref "Q3") (pin "3") (pinfunction "D_3") (pintype "passive"))
    )
    (net (code "51") (name "Net-(D2-PadA)") (class "Default")
      (node (ref "D2") (pin "A") (pinfunction "A_A") (pintype "passive"))
      (node (ref "R13") (pin "2") (pinfunction "2_2") (pintype "passive"))
    )
    (net (code "52") (name "Net-(J1-BLUE)") (class "Default")
      (node (ref "J1") (pin "3") (pinfunction "BLUE_3") (pintype "passive"))
      (node (ref "R5") (pin "2") (pinfunction "2_2") (pintype "passive"))
      (node (ref "R6") (pin "2") (pinfunction "2_2") (pintype "passive"))
    )
    (net (code "53") (name "Net-(J1-GREEN)") (class "Default")
      (node (ref "J1") (pin "2") (pinfunction "GREEN_2") (pintype "passive"))
      (node (ref "R3") (pin "2") (pinfunction "2_2") (pintype "passive"))
      (node (ref "R4") (pin "2") (pinfunction "2_2") (pintype "passive"))
    )
    (net (code "54") (name "Net-(J1-RED)") (class "Default")
      (node (ref "J1") (pin "1") (pinfunction "RED_1") (pintype "passive"))
      (node (ref "R1") (pin "2") (pinfunction "2_2") (pintype "passive"))
      (node (ref "R2") (pin "2") (pinfunction "2_2") (pintype "passive"))
    )
    (net (code "55") (name "unconnected-(J1-ID0-Pad11)") (class "Default")
      (node (ref "J1") (pin "11") (pinfunction "ID0_11") (pintype "passive"))
    )
    (net (code "56") (name "unconnected-(J1-ID1{slash}SDA-Pad12)") (class "Default")
      (node (ref "J1") (pin "12") (pinfunction "ID1/SDA_12") (pintype "passive"))
    )
    (net (code "57") (name "unconnected-(J1-ID2-Pad4)") (class "Default")
      (node (ref "J1") (pin "4") (pinfunction "ID2_4") (pintype "passive"))
    )
    (net (code "58") (name "unconnected-(J1-ID3{slash}SCL-Pad15)") (class "Default")
      (node (ref "J1") (pin "15") (pinfunction "ID3/SCL_15") (pintype "passive"))
    )
    (net (code "59") (name "unconnected-(J1-KEY-Pad9)") (class "Default")
      (node (ref "J1") (pin "9") (pinfunction "KEY_9") (pintype "passive"))
    )
    (net (code "60") (name "unconnected-(J2-NC-Pad2)") (class "Default")
      (node (ref "J2") (pin "2") (pinfunction "NC_2") (pintype "passive+no_connect"))
    )
    (net (code "61") (name "unconnected-(J2-NC-Pad6)") (class "Default")
      (node (ref "J2") (pin "6") (pinfunction "NC_6") (pintype "passive+no_connect"))
    )
    (net (code "62") (name "unconnected-(J3-NC-Pad2)") (class "Default")
      (node (ref "J3") (pin "2") (pinfunction "NC_2") (pintype "passive+no_connect"))
    )
    (net (code "63") (name "unconnected-(J3-NC-Pad6)") (class "Default")
      (node (ref "J3") (pin "6") (pinfunction "NC_6") (pintype "passive+no_connect"))
    )
    (net (code "64") (name "unconnected-(P2-GND-Pad5)") (class "Default")
      (node (ref "P2") (pin "5") (pinfunction "GND_5") (pintype "power_in+no_connect"))
    )
    (net (code "65") (name "unconnected-(P2-GND-Pad11)") (class "Default")
      (node (ref "P2") (pin "11") (pinfunction "GND_11") (pintype "power_in+no_connect"))
    )
    (net (code "66") (name "unconnected-(P2-VCC-Pad6)") (class "Default")
      (node (ref "P2") (pin "6") (pinfunction "VCC_6") (pintype "power_in+no_connect"))
    )
    (net (code "67") (name "unconnected-(P2-VCC-Pad12)") (class "Default")
      (node (ref "P2") (pin "12") (pinfunction "VCC_12") (pintype "power_in+no_connect"))
    )
    (net (code "68") (name "unconnected-(P4-GND-Pad5)") (class "Default")
      (node (ref "P4") (pin "5") (pinfunction "GND_5") (pintype "power_in+no_connect"))
    )
    (net (code "69") (name "unconnected-(P4-GND-Pad11)") (class "Default")
      (node (ref "P4") (pin "11") (pinfunction "GND_11") (pintype "power_in+no_connect"))
    )
    (net (code "70") (name "unconnected-(P4-VCC-Pad6)") (class "Default")
      (node (ref "P4") (pin "6") (pinfunction "VCC_6") (pintype "power_in+no_connect"))
    )
    (net (code "71") (name "unconnected-(P4-VCC-Pad12)") (class "Default")
      (node (ref "P4") (pin "12") (pinfunction "VCC_12") (pintype "power_in+no_connect"))
    )
    (net (code "72") (name "unconnected-(P6-GND-Pad5)") (class "Default")
      (node (ref "P6") (pin "5") (pinfunction "GND_5") (pintype "power_in"))
    )
    (net (code "73") (name "unconnected-(P6-GND-Pad11)") (class "Default")
      (node (ref "P6") (pin "11") (pinfunction "GND_11") (pintype "power_in+no_connect"))
    )
    (net (code "74") (name "unconnected-(P6-VCC-Pad6)") (class "Default")
      (node (ref "P6") (pin "6") (pinfunction "VCC_6") (pintype "power_in"))
    )
    (net (code "75") (name "unconnected-(P6-VCC-Pad12)") (class "Default")
      (node (ref "P6") (pin "12") (pinfunction "VCC_12") (pintype "power_in+no_connect"))
    )
  )
)
